# 8V_Buck_LDO_Power.net
KiCad netlist of a schematic drawn in Altium Designer
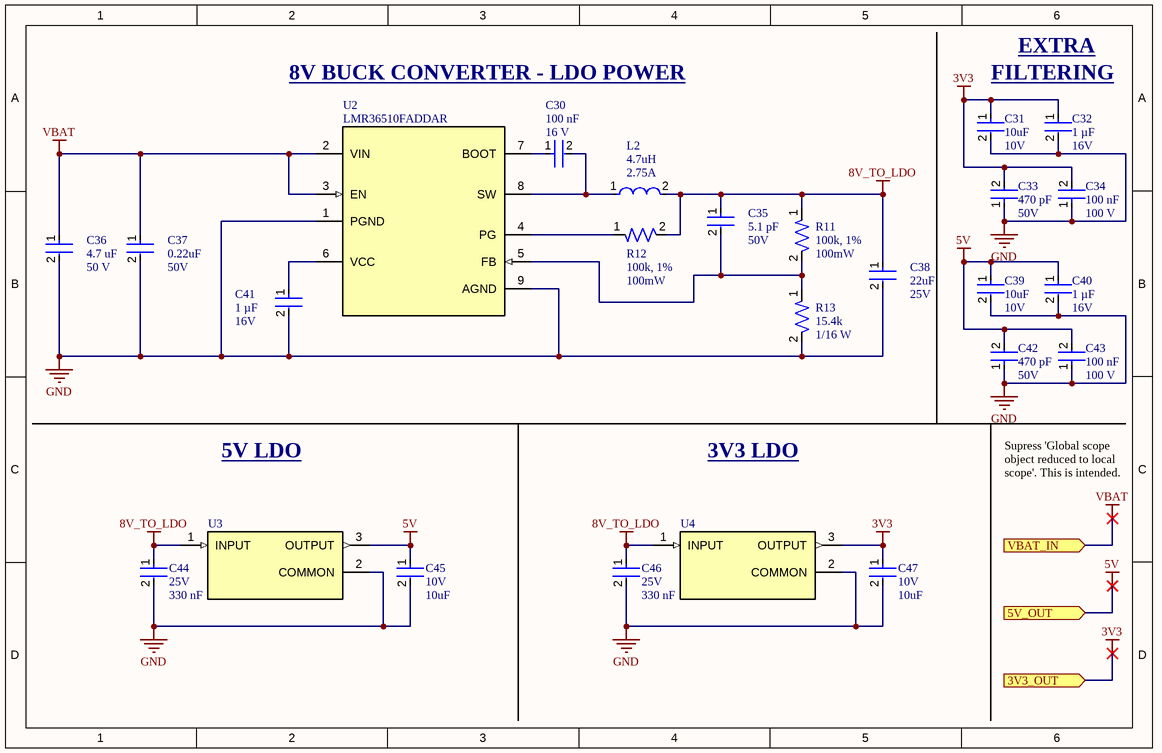
[diagram p0: 8V_Buck_LDO_Power.SchDoc]

(export (version "E")
  (design (tool "Eeschema 10.0.6"))
  (components
    (comp (ref "C30")
      (value "CC0402KRX7R7BB104")
      (footprint "FP-CC0402-IPC_B")
      (description "CAP CER 0.1UF 16V X7R 0402")
      (fields
        (field (name "MANUFACTURER") "YAGEO")
        (field (name "TOLERANCE") "0.1")
        (field (name "VOLTAGE RATING") "16 V")
        (field (name "CAPACITANCE") "100 nF")
      )
      (libsource (lib "JLC_25") (part "CAP-0.1U-0001"))
    )
    (comp (ref "C31")
      (value "CC0603KRX5R6BB106")
      (footprint "FP-CC0603-DC-MFG")
      (description "CAP CER 10UF 10V X5R 0603")
      (fields
        (field (name "TOLERANCE") "10%")
        (field (name "RATED VOLTAGE") "10V")
        (field (name "CAPACITANCE") "10uF")
      )
      (libsource (lib "JLC_25") (part "CAP-10U-0001"))
    )
    (comp (ref "C32")
      (value "CC0603KRX7R7BB105")
      (footprint "FP-CC0603-DA-MFG")
      (description "1 µF ±10% 16V Ceramic Capacitor X7R 0603 (1608 Metric)")
      (fields (field (name "CAPACITANCE") "1 µF") (field (name "VOLTAGE") "16V"))
      (libsource (lib "JLC_25") (part "CAP-1U-0002"))
    )
    (comp (ref "C33")
      (value "CC0805JRNPO9BN471")
      (footprint "CAP_CC0805_YAG-L")
      (description "CAP CER 470PF 50V C0G/NPO 0805")
      (fields (field (name "VOLTAGE") "50V") (field (name "CAPACITANCE") "470 pF"))
      (libsource (lib "JLC_25") (part "CAP-470P-0001"))
    )
    (comp (ref "C34")
      (value "CC0603KRX7R0BB104")
      (footprint "CAP-0603")
      (description "0.1 µF ±10% 100V Ceramic Capacitor X7R 0603 (1608 Metric)")
      (fields (field (name "CAPACITANCE") "100 nF") (field (name "VOLTAGE") "100 V"))
      (libsource (lib "JLC_25") (part "CAP-100N-0001"))
    )
    (comp (ref "C35")
      (value "CC0402CRNPO9BN5R1")
      (footprint "CAPC1005X55N")
      (description "5.1pF Â±0.25pF 50V Ceramic Capacitor C0G, NP0 0402 (1005 Metric)")
      (fields
        (field (name "MF") "Yageo")
        (field (name "VOLTAGE RATING") "50V")
        (field (name "CAPACITANCE") "5.1 pF")
      )
      (libsource (lib "JLC_25") (part "CAP-5.1P-0001"))
    )
    (comp (ref "C36")
      (value "CC0805KKX5R9BB475")
      (footprint "FP-CC0805-0_85-MFG")
      (description "CAP CER 4.7UF 50V X5R 0805")
      (fields
        (field (name "MANUFACTURER") "Yageo")
        (field (name "OCTOPART") "https://octopart.com/cc0805kkx5r9bb475-yageo-81932641")
        (field (name "VOLTAGE RATING") "50 V")
        (field (name "CAPACITANCE") "4.7 uF")
      )
      (libsource (lib "JLC_25") (part "CAP-4.7U-0002"))
    )
    (comp (ref "C37")
      (value "CC0603JRX7R9BB224")
      (footprint "CAP_CC0603_YAG")
      (description "0.22 µF ±5% 50V Ceramic Capacitor X7R 0603 (1608 Metric)")
      (fields (field (name "CAPACITANCE") "0.22uF") (field (name "VOLTAGE") "50V"))
      (libsource (lib "JLC_25") (part "CAP-0.22U-0001"))
    )
    (comp (ref "C38")
      (value "GRM32ER61E226KE15L")
      (footprint "FP-GRM32-MFG")
      (description "CAP CER 22UF 25V X5R 1210")
      (fields
        (field (name "TOLERANCE") "10%")
        (field (name "MANUFACTURER") "Murata Electronics North America")
        (field (name "VOLTAGE - RATED") "25V")
        (field (name "CAPACITANCE") "22uF")
      )
      (libsource (lib "JLC_25") (part "CAP-22U-0001"))
    )
    (comp (ref "C39")
      (value "CC0603KRX5R6BB106")
      (footprint "FP-CC0603-DC-MFG")
      (description "CAP CER 10UF 10V X5R 0603")
      (fields
        (field (name "TOLERANCE") "10%")
        (field (name "RATED VOLTAGE") "10V")
        (field (name "CAPACITANCE") "10uF")
      )
      (libsource (lib "JLC_25") (part "CAP-10U-0001"))
    )
    (comp (ref "C40")
      (value "CC0603KRX7R7BB105")
      (footprint "FP-CC0603-DA-MFG")
      (description "1 µF ±10% 16V Ceramic Capacitor X7R 0603 (1608 Metric)")
      (fields (field (name "CAPACITANCE") "1 µF") (field (name "VOLTAGE") "16V"))
      (libsource (lib "JLC_25") (part "CAP-1U-0002"))
    )
    (comp (ref "C41")
      (value "CC0603KRX7R7BB105")
      (footprint "FP-CC0603-DA-MFG")
      (description "1 µF ±10% 16V Ceramic Capacitor X7R 0603 (1608 Metric)")
      (fields (field (name "CAPACITANCE") "1 µF") (field (name "VOLTAGE") "16V"))
      (libsource (lib "JLC_25") (part "CAP-1U-0002"))
    )
    (comp (ref "C42")
      (value "CC0805JRNPO9BN471")
      (footprint "CAP_CC0805_YAG-L")
      (description "CAP CER 470PF 50V C0G/NPO 0805")
      (fields (field (name "VOLTAGE") "50V") (field (name "CAPACITANCE") "470 pF"))
      (libsource (lib "JLC_25") (part "CAP-470P-0001"))
    )
    (comp (ref "C43")
      (value "CC0603KRX7R0BB104")
      (footprint "CAP-0603")
      (description "0.1 µF ±10% 100V Ceramic Capacitor X7R 0603 (1608 Metric)")
      (fields (field (name "CAPACITANCE") "100 nF") (field (name "VOLTAGE") "100 V"))
      (libsource (lib "JLC_25") (part "CAP-100N-0001"))
    )
    (comp (ref "C44")
      (value "CC0603KRX7R8BB334")
      (footprint "FP-CC0603-DA-MFG")
      (description "CAP CER 0.33UF 25V X7R 0603")
      (fields
        (field (name "VOLTAGE") "25 V")
        (field (name "OCTOPART") "https://octopart.com/cc0603krx7r8bb334-yageo-47255252")
        (field (name "RATED VOLTAGE") "25V")
        (field (name "CAPACITANCE") "330 nF")
      )
      (libsource (lib "JLC_25") (part "CAP-0.33U-0001"))
    )
    (comp (ref "C45")
      (value "CC0603KRX5R6BB106")
      (footprint "FP-CC0603-DC-MFG")
      (description "CAP CER 10UF 10V X5R 0603")
      (fields
        (field (name "TOLERANCE") "10%")
        (field (name "RATED VOLTAGE") "10V")
        (field (name "CAPACITANCE") "10uF")
      )
      (libsource (lib "JLC_25") (part "CAP-10U-0001"))
    )
    (comp (ref "C46")
      (value "CC0603KRX7R8BB334")
      (footprint "FP-CC0603-DA-MFG")
      (description "CAP CER 0.33UF 25V X7R 0603")
      (fields
        (field (name "VOLTAGE") "25 V")
        (field (name "OCTOPART") "https://octopart.com/cc0603krx7r8bb334-yageo-47255252")
        (field (name "RATED VOLTAGE") "25V")
        (field (name "CAPACITANCE") "330 nF")
      )
      (libsource (lib "JLC_25") (part "CAP-0.33U-0001"))
    )
    (comp (ref "C47")
      (value "CC0603KRX5R6BB106")
      (footprint "FP-CC0603-DC-MFG")
      (description "CAP CER 10UF 10V X5R 0603")
      (fields
        (field (name "TOLERANCE") "10%")
        (field (name "RATED VOLTAGE") "10V")
        (field (name "CAPACITANCE") "10uF")
      )
      (libsource (lib "JLC_25") (part "CAP-10U-0001"))
    )
    (comp (ref "L2")
      (value "CDRH104NP-221MC")
      (footprint "IND-4.7UH-0001")
      (description "FIXED IND 220UH 520MA 960MOHM SM")
      (fields (field (name "INDUCTANCE") "4.7uH") (field (name "CURRENT RATING") "2.75A"))
      (libsource (lib "JLC_25") (part "IND-4.7U-0001"))
    )
    (comp (ref "R11")
      (value "RC0603FR-07100KL")
      (footprint "FP-RC0603-0_55-IPC_B")
      (description "RES SMD 100K OHM 1% 1/10W 0603")
      (fields
        (field (name "TOLERANCE") "1%")
        (field (name "POWER") "100mW")
        (field (name "RESISTANCE") "100k, 1%")
      )
      (libsource (lib "JLC_25") (part "RES-100k-0001"))
    )
    (comp (ref "R12")
      (value "RC0603FR-07100KL")
      (footprint "FP-RC0603-0_55-IPC_B")
      (description "RES SMD 100K OHM 1% 1/10W 0603")
      (fields
        (field (name "TOLERANCE") "1%")
        (field (name "POWER") "100mW")
        (field (name "RESISTANCE") "100k, 1%")
      )
      (libsource (lib "JLC_25") (part "RES-100k-0001"))
    )
    (comp (ref "R13")
      (value "AC0402FR-0715K4L")
      (footprint "FP-AC0402-MFG")
      (description "RES 15.4kΩ ±1% 0.063W 0402")
      (fields
        (field (name "TOLERANCE") "1%")
        (field (name "POWER RATING") "1/16 W")
        (field (name "RESISTANCE") "15.4k")
      )
      (libsource (lib "JLC_25") (part "RES-15.4K-0001"))
    )
    (comp (ref "U2")
      (value "LMR36510FADDAR")
      (footprint "DDA0008J")
      (description "Buck Switching Regulator IC Positive Adjustable 1V 1 Output 1A 8-PowerSOIC (0.154\", 3.90mm Width)")
      (libsource (lib "JLC_25") (part "IC-BUCK-0003"))
    )
    (comp (ref "U3")
      (value "UA78M05IDCYR")
      (footprint "FP-DCY0004A-IPC_B")
      (description "IC REG LINEAR 5V 500MA SOT223-4")
      (fields
        (field (name "OCTOPART") "https://octopart.com/ua78m05idcyr-texas+instruments-525575")
        (field (name "MANUFACTURER") "Texas Instruments")
      )
      (libsource (lib "JLC_25") (part "IC-LDO-0001"))
    )
    (comp (ref "U4")
      (value "UA78M33CDCYR")
      (footprint "VREG_UA78M33CDCYR")
      (description "IC REG LIN 3.3V 500MA SOT223-4")
      (fields (field (name "MF") "Texas Instruments"))
      (libsource (lib "JLC_25") (part "IC-LDO-0002"))
    )
  )
  (nets
    (net (code "1") (name "3V3") (class "Default")
      (node (ref "C31") (pin "1") (pinfunction "1_1") (pintype "passive"))
      (node (ref "C32") (pin "1") (pinfunction "1_1") (pintype "passive"))
      (node (ref "C33") (pin "2") (pinfunction "2_2") (pintype "passive"))
      (node (ref "C34") (pin "2") (pinfunction "2_2") (pintype "passive"))
      (node (ref "C47") (pin "1") (pinfunction "1_1") (pintype "passive"))
      (node (ref "U4") (pin "3") (pinfunction "OUTPUT_3") (pintype "output"))
    )
    (net (code "2") (name "5V") (class "Default")
      (node (ref "C39") (pin "1") (pinfunction "1_1") (pintype "passive"))
      (node (ref "C40") (pin "1") (pinfunction "1_1") (pintype "passive"))
      (node (ref "C42") (pin "2") (pinfunction "2_2") (pintype "passive"))
      (node (ref "C43") (pin "2") (pinfunction "2_2") (pintype "passive"))
      (node (ref "C45") (pin "1") (pinfunction "1_1") (pintype "passive"))
      (node (ref "U3") (pin "3") (pinfunction "OUTPUT_3") (pintype "output"))
    )
    (net (code "3") (name "8V_TO_LDO") (class "Default")
      (node (ref "C35") (pin "1") (pinfunction "1_1") (pintype "passive"))
      (node (ref "C38") (pin "1") (pinfunction "1_1") (pintype "passive"))
      (node (ref "C44") (pin "1") (pinfunction "1_1") (pintype "passive"))
      (node (ref "C46") (pin "1") (pinfunction "1_1") (pintype "passive"))
      (node (ref "L2") (pin "2") (pinfunction "2_2") (pintype "passive"))
      (node (ref "R11") (pin "1") (pinfunction "1_1") (pintype "passive"))
      (node (ref "R12") (pin "2") (pinfunction "2_2") (pintype "passive"))
      (node (ref "U3") (pin "1") (pinfunction "INPUT_1") (pintype "input"))
      (node (ref "U4") (pin "1") (pinfunction "INPUT_1") (pintype "input"))
    )
    (net (code "4") (name "GND") (class "Default")
      (node (ref "C31") (pin "2") (pinfunction "2_2") (pintype "passive"))
      (node (ref "C32") (pin "2") (pinfunction "2_2") (pintype "passive"))
      (node (ref "C33") (pin "1") (pinfunction "1_1") (pintype "passive"))
      (node (ref "C34") (pin "1") (pinfunction "1_1") (pintype "passive"))
      (node (ref "C36") (pin "2") (pinfunction "2_2") (pintype "passive"))
      (node (ref "C37") (pin "2") (pinfunction "2_2") (pintype "passive"))
      (node (ref "C38") (pin "2") (pinfunction "2_2") (pintype "passive"))
      (node (ref "C39") (pin "2") (pinfunction "2_2") (pintype "passive"))
      (node (ref "C40") (pin "2") (pinfunction "2_2") (pintype "passive"))
      (node (ref "C41") (pin "2") (pinfunction "2_2") (pintype "passive"))
      (node (ref "C42") (pin "1") (pinfunction "1_1") (pintype "passive"))
      (node (ref "C43") (pin "1") (pinfunction "1_1") (pintype "passive"))
      (node (ref "C44") (pin "2") (pinfunction "2_2") (pintype "passive"))
      (node (ref "C45") (pin "2") (pinfunction "2_2") (pintype "passive"))
      (node (ref "C46") (pin "2") (pinfunction "2_2") (pintype "passive"))
      (node (ref "C47") (pin "2") (pinfunction "2_2") (pintype "passive"))
      (node (ref "R13") (pin "2") (pinfunction "2_2") (pintype "passive"))
      (node (ref "U2") (pin "1") (pinfunction "PGND_1") (pintype "power_in"))
      (node (ref "U2") (pin "9") (pinfunction "AGND_9") (pintype "passive"))
      (node (ref "U3") (pin "2") (pinfunction "COMMON_2") (pintype "passive"))
      (node (ref "U4") (pin "2") (pinfunction "COMMON_2") (pintype "power_in"))
    )
    (net (code "5") (name "Net-(U2-BOOT)") (class "Default")
      (node (ref "C30") (pin "1") (pinfunction "1_1") (pintype "passive"))
      (node (ref "U2") (pin "7") (pinfunction "BOOT_7") (pintype "power_in"))
    )
    (net (code "6") (name "Net-(U2-FB)") (class "Default")
      (node (ref "C35") (pin "2") (pinfunction "2_2") (pintype "passive"))
      (node (ref "R11") (pin "2") (pinfunction "2_2") (pintype "passive"))
      (node (ref "R13") (pin "1") (pinfunction "1_1") (pintype "passive"))
      (node (ref "U2") (pin "5") (pinfunction "FB_5") (pintype "input"))
    )
    (net (code "7") (name "Net-(U2-PG)") (class "Default")
      (node (ref "R12") (pin "1") (pinfunction "1_1") (pintype "passive"))
      (node (ref "U2") (pin "4") (pinfunction "PG_4") (pintype "open_collector"))
    )
    (net (code "8") (name "Net-(U2-SW)") (class "Default")
      (node (ref "C30") (pin "2") (pinfunction "2_2") (pintype "passive"))
      (node (ref "L2") (pin "1") (pinfunction "1_1") (pintype "passive"))
      (node (ref "U2") (pin "8") (pinfunction "SW_8") (pintype "power_in"))
    )
    (net (code "9") (name "Net-(U2-VCC)") (class "Default")
      (node (ref "C41") (pin "1") (pinfunction "1_1") (pintype "passive"))
      (node (ref "U2") (pin "6") (pinfunction "VCC_6") (pintype "power_in"))
    )
    (net (code "10") (name "VBAT") (class "Default")
      (node (ref "C36") (pin "1") (pinfunction "1_1") (pintype "passive"))
      (node (ref "C37") (pin "1") (pinfunction "1_1") (pintype "passive"))
      (node (ref "U2") (pin "2") (pinfunction "VIN_2") (pintype "power_in"))
      (node (ref "U2") (pin "3") (pinfunction "EN_3") (pintype "input"))
    )
  )
)
